# esp-wroom-32.net
KiCad netlist of a schematic drawn in Altium Designer
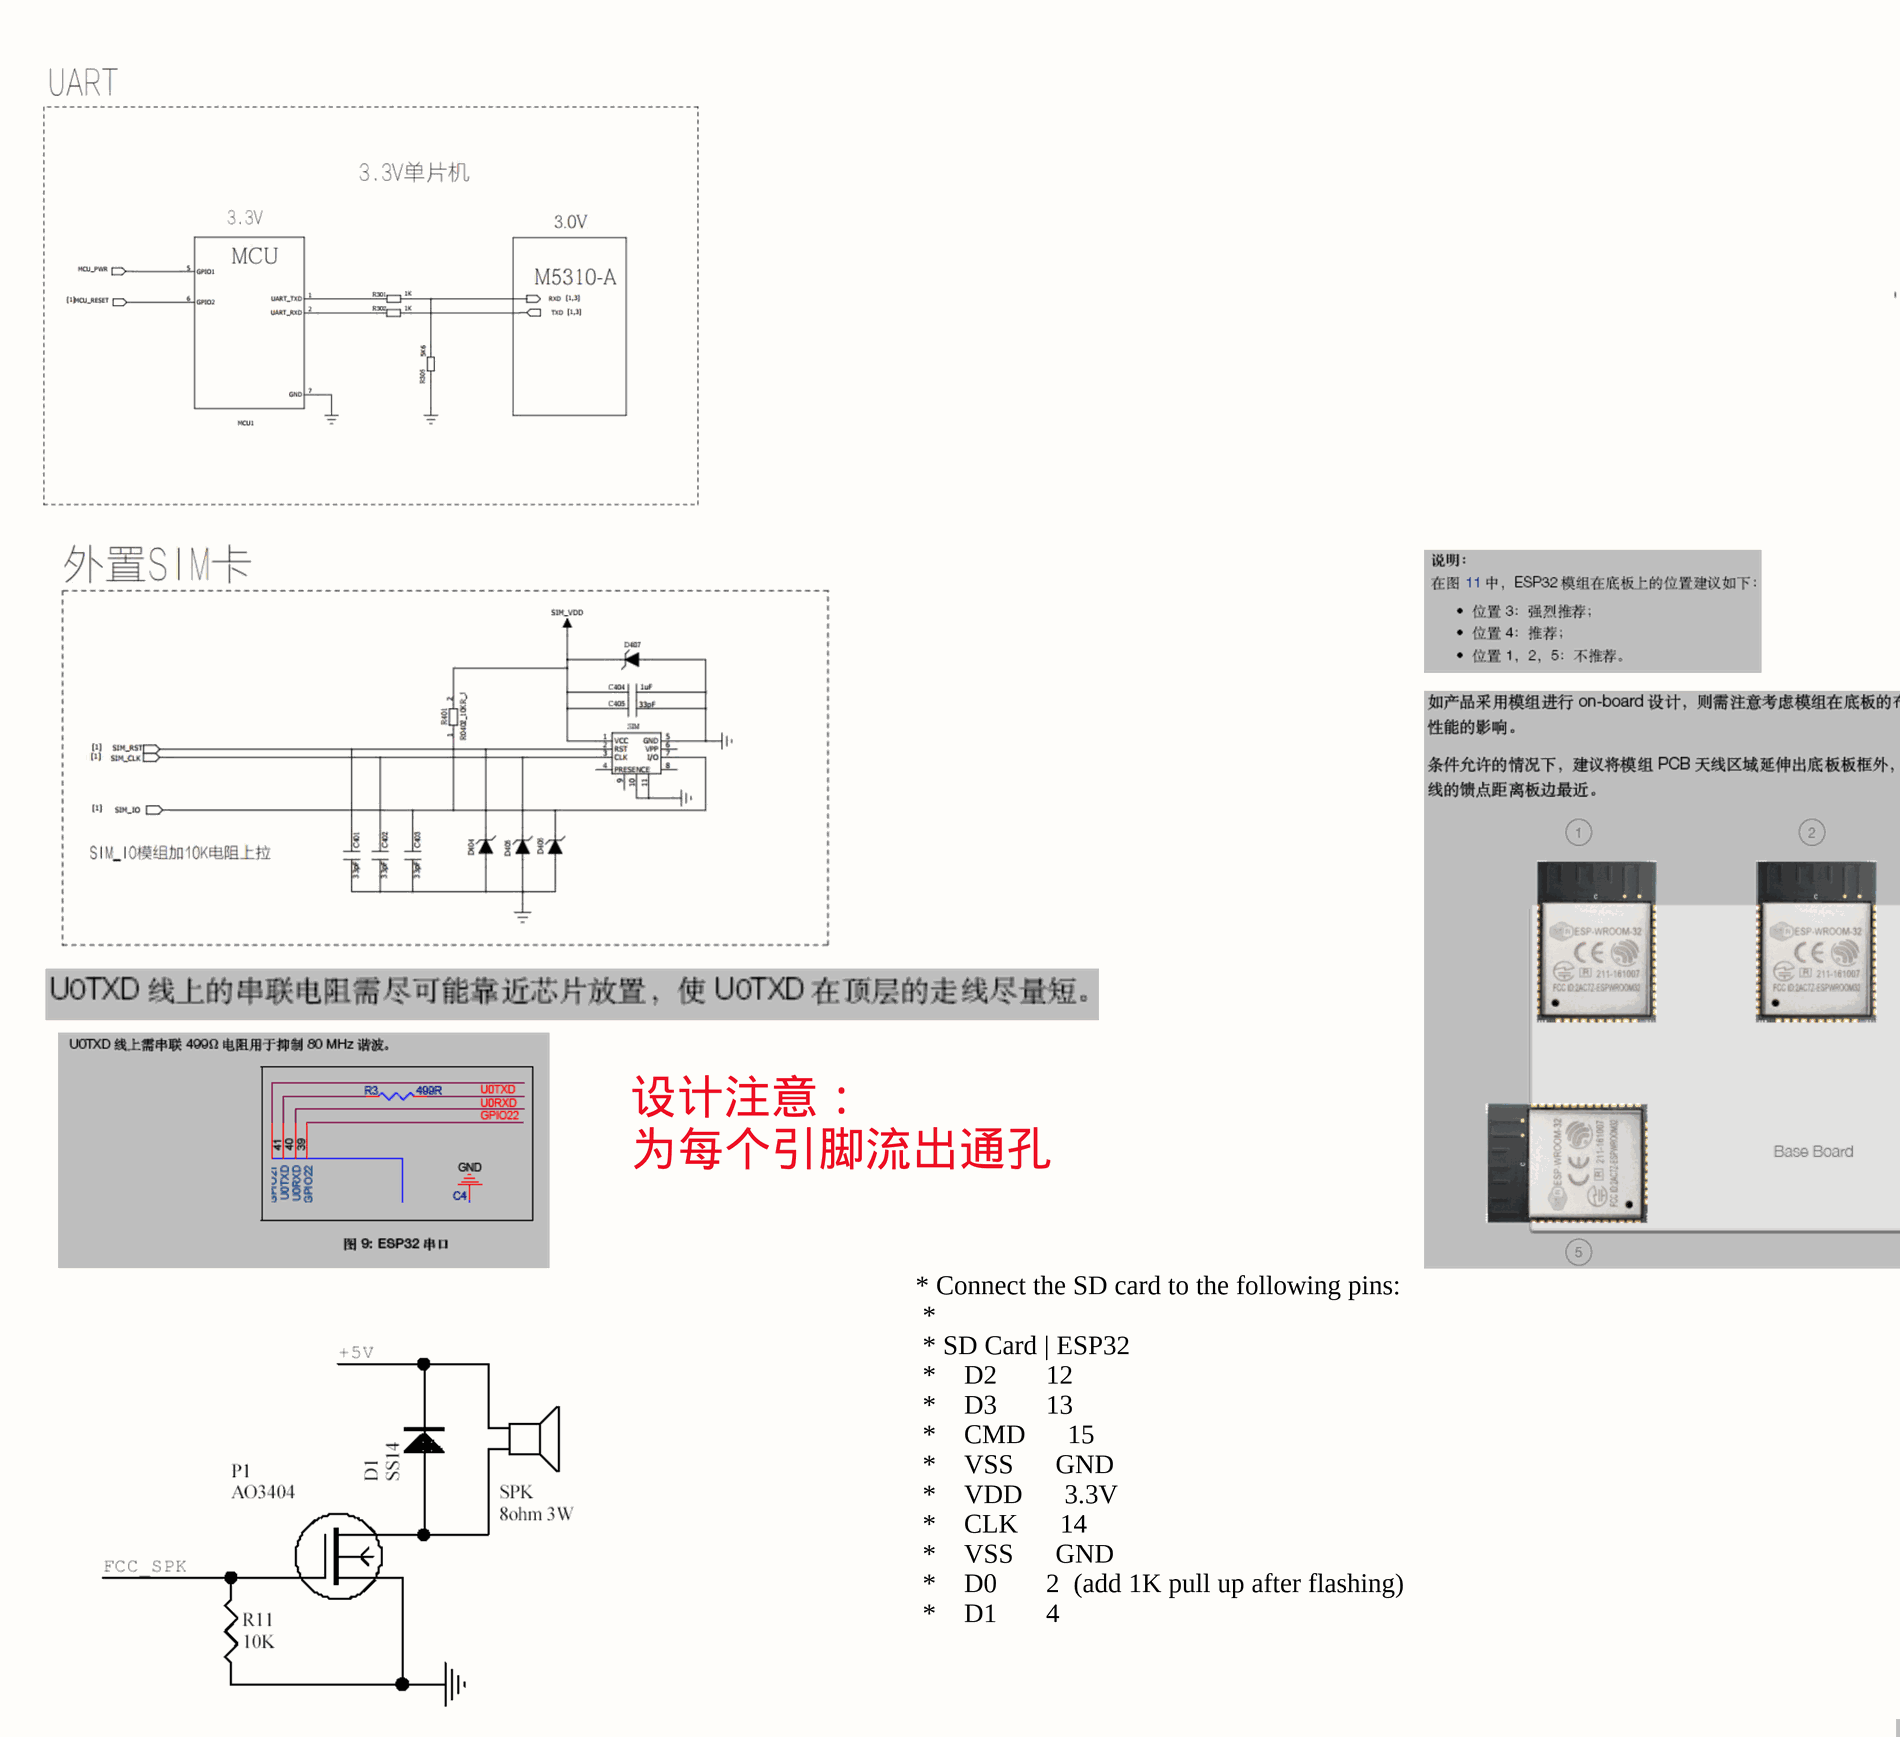
[diagram p0: esp-wroom-32.SchDoc, top left]
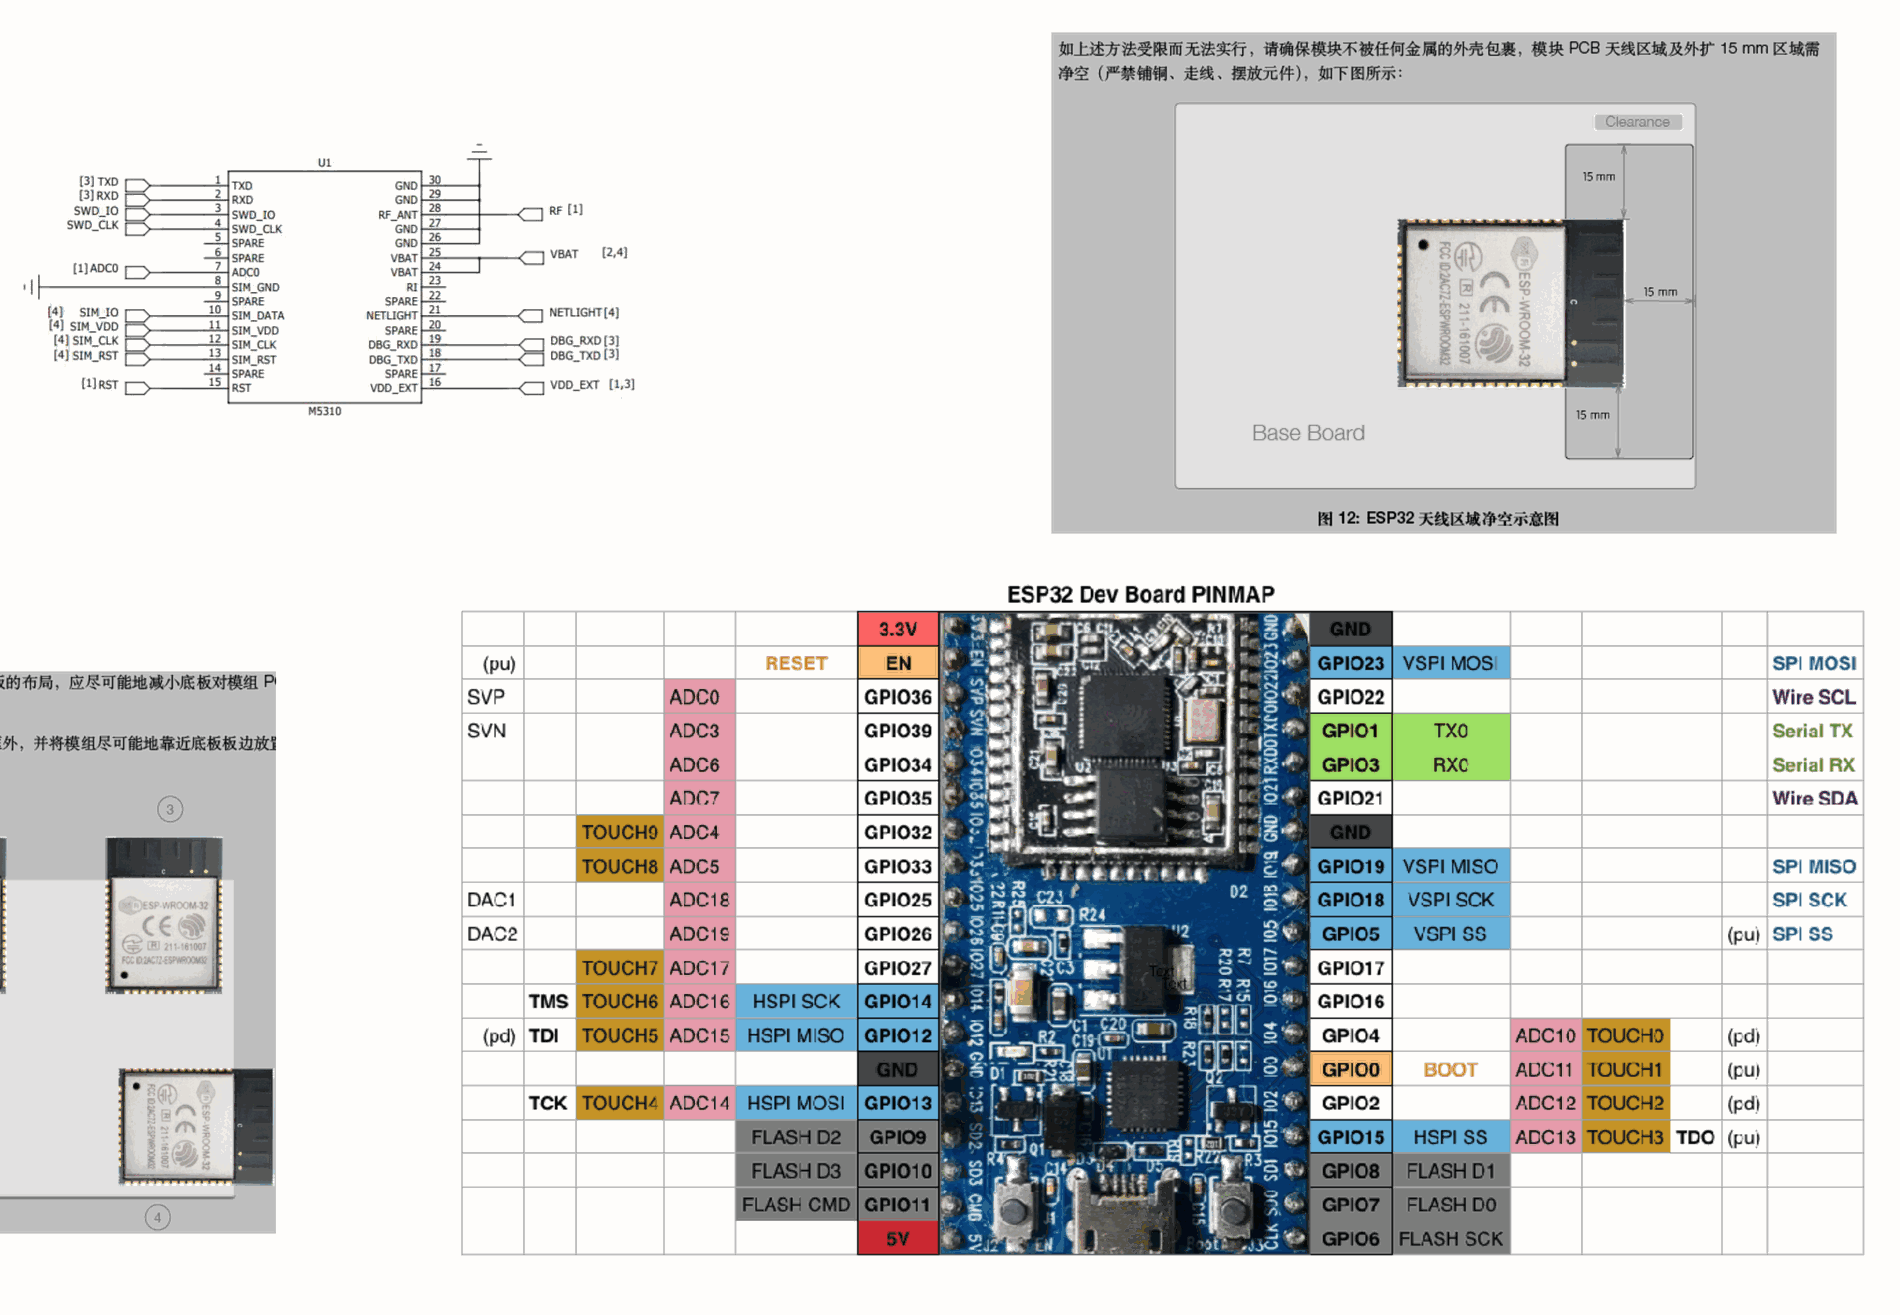
[diagram p1: esp-wroom-32.SchDoc, top right]
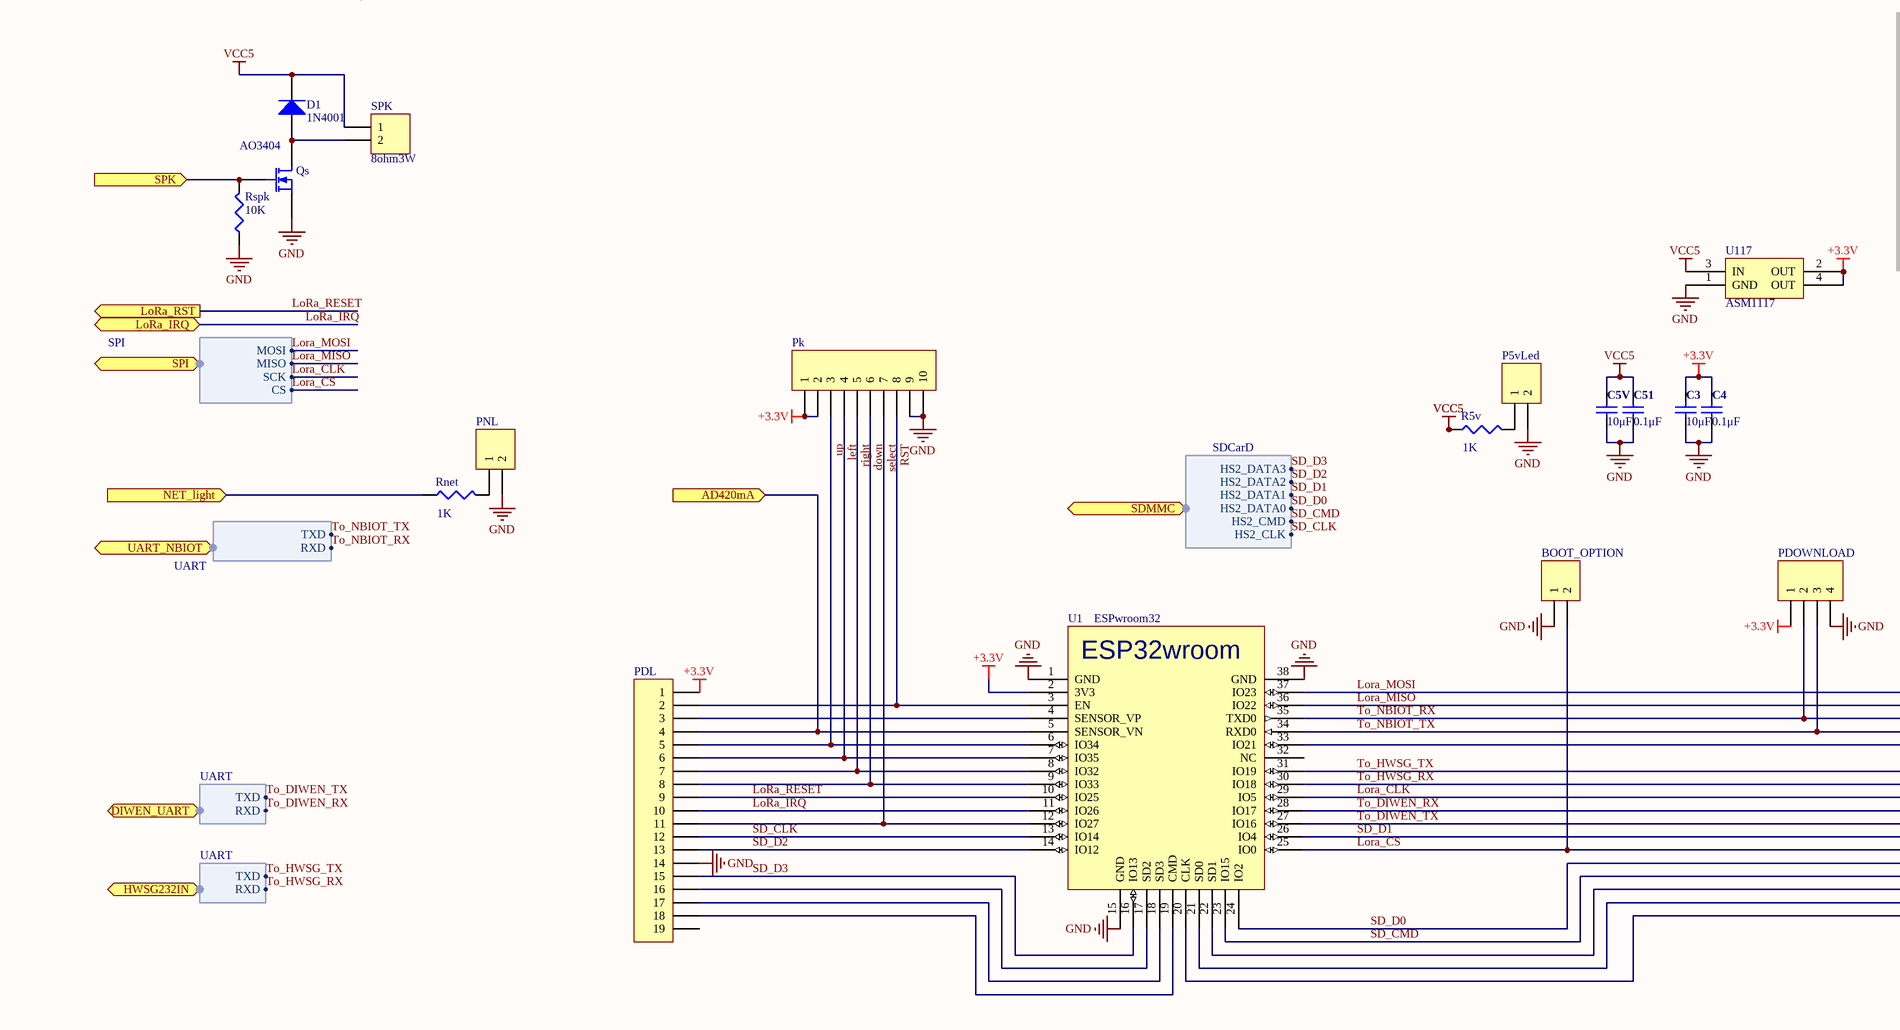
[diagram p2: esp-wroom-32.SchDoc, bottom left]
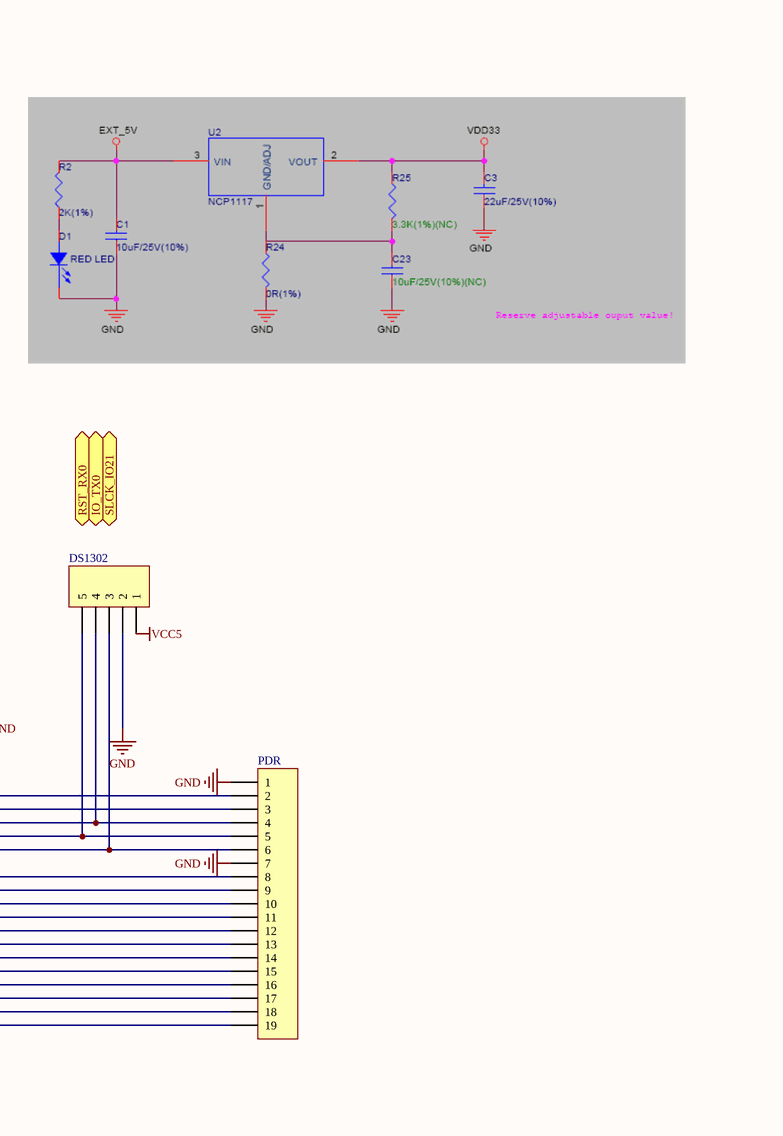
[diagram p3: esp-wroom-32.SchDoc, bottom right]

(export (version "E")
  (design (tool "Eeschema 10.0.6"))
  (components
    (comp (ref "BOOT_OPTION")
      (value "Header 2")
      (footprint "HDR1X2")
      (description "Header, 2-Pin")
      (fields (field (name "PUBLISHER") "Altium Limited"))
      (libsource (lib "Miscellaneous Connectors") (part "Header 2"))
    )
    (comp (ref "C3")
      (value "10μF")
      (footprint "CAP-7343")
      (description "贴片电容")
      (libsource (lib "FourAxis") (part "Cap"))
    )
    (comp (ref "C4")
      (value "0.1μF")
      (footprint "0805-1")
      (description "贴片电容")
      (libsource (lib "FourAxis") (part "Cap"))
    )
    (comp (ref "C5V")
      (value "10μF")
      (footprint "CAP-7343")
      (description "贴片电容")
      (libsource (lib "FourAxis") (part "Cap"))
    )
    (comp (ref "C51")
      (value "0.1μF")
      (footprint "0805-1")
      (description "贴片电容")
      (libsource (lib "FourAxis") (part "Cap"))
    )
    (comp (ref "D1")
      (value "SS14")
      (footprint "DIODE-1206")
      (description "二极管")
      (fields (field (name "TYPE") "1N4001") (field (name "PUBLISHER") "Altium Limited"))
      (libsource (lib "Fszhang") (part "Diode"))
    )
    (comp (ref "DS1302")
      (value "Header 5")
      (footprint "HDR1X5")
      (description "Header, 5-Pin")
      (fields (field (name "PUBLISHER") "Altium Limited"))
      (libsource (lib "Miscellaneous Connectors") (part "Header 5"))
    )
    (comp (ref "P5vLed")
      (value "Header 2")
      (footprint "HDR1X2")
      (description "Header, 2-Pin")
      (fields (field (name "PUBLISHER") "Altium Limited"))
      (libsource (lib "Miscellaneous Connectors") (part "Header 2"))
    )
    (comp (ref "PDL")
      (value "Header 19")
      (footprint "HDR1X19")
      (description "Header, 19-Pin")
      (fields (field (name "PUBLISHER") "Altium Limited"))
      (libsource (lib "Miscellaneous Connectors") (part "Header 19"))
    )
    (comp (ref "PDOWNLOAD")
      (value "Header 4")
      (footprint "HDR1X4")
      (description "Header, 4-Pin")
      (fields (field (name "PUBLISHER") "Altium Limited"))
      (libsource (lib "Miscellaneous Connectors") (part "Header 4"))
    )
    (comp (ref "PDR")
      (value "Header 19")
      (footprint "HDR1X19")
      (description "Header, 19-Pin")
      (fields (field (name "PUBLISHER") "Altium Limited"))
      (libsource (lib "") (part "Header 19_1"))
    )
    (comp (ref "Pk")
      (value "Header 10")
      (footprint "HDR1X10")
      (description "Header, 10-Pin")
      (fields (field (name "PUBLISHER") "Altium Limited"))
      (libsource (lib "Miscellaneous Connectors") (part "Header 10"))
    )
    (comp (ref "PNL")
      (value "Header 2")
      (footprint "HDR1X2")
      (description "Header, 2-Pin")
      (fields (field (name "PUBLISHER") "Altium Limited"))
      (libsource (lib "Miscellaneous Connectors") (part "Header 2"))
    )
    (comp (ref "Qs")
      (value "AO3404")
      (footprint "E3")
      (description "N-Channel MOSFET")
      (fields (field (name "PUBLISHER") "Altium Limited"))
      (libsource (lib "Miscellaneous Devices") (part "MOSFET-N"))
    )
    (comp (ref "R5v")
      (value "1K")
      (footprint "0805")
      (description "Resistor")
      (fields (field (name "Comment") "Res3") (field (name "PUBLISHER") "Altium Limited"))
      (libsource (lib "Miscellaneous Devices") (part "Res3"))
    )
    (comp (ref "Rnet")
      (value "1K")
      (footprint "0805")
      (description "Resistor")
      (fields (field (name "Comment") "Res3") (field (name "PUBLISHER") "Altium Limited"))
      (libsource (lib "Miscellaneous Devices") (part "Res3"))
    )
    (comp (ref "Rspk")
      (value "10K")
      (footprint "0805")
      (description "Resistor")
      (fields (field (name "Comment") "Res3") (field (name "PUBLISHER") "Altium Limited"))
      (libsource (lib "Miscellaneous Devices") (part "Res3"))
    )
    (comp (ref "SPK")
      (value "8ohm3W")
      (footprint "HDR1X2")
      (description "Header, 2-Pin")
      (fields (field (name "PUBLISHER") "Altium Limited"))
      (libsource (lib "") (part "Header 2_1"))
    )
    (comp (ref "U1")
      (value "ESPwroom32")
      (footprint "PCBComponent_1 - duplicate")
      (libsource (lib "ESPlib") (part "ESPwroom32"))
    )
    (comp (ref "U117")
      (value "ASM1117")
      (footprint "SOT-223")
      (description "3.3V稳压芯片")
      (libsource (lib "Fszhang") (part "ASM1117"))
    )
  )
  (nets
    (net (code "4") (name "+3.3V") (class "Default")
      (node (ref "C3") (pin "2") (pinfunction "2_2") (pintype "passive"))
      (node (ref "C4") (pin "2") (pinfunction "2_2") (pintype "passive"))
      (node (ref "PDL") (pin "1") (pinfunction "1_1") (pintype "passive"))
      (node (ref "PDOWNLOAD") (pin "1") (pinfunction "1_1") (pintype "passive"))
      (node (ref "Pk") (pin "1") (pinfunction "1_1") (pintype "passive"))
      (node (ref "Pk") (pin "2") (pinfunction "2_2") (pintype "passive"))
      (node (ref "U1") (pin "2") (pinfunction "3V3_2") (pintype "power_in"))
      (node (ref "U117") (pin "2") (pinfunction "OUT_2") (pintype "passive"))
      (node (ref "U117") (pin "4") (pinfunction "OUT_4") (pintype "passive"))
    )
    (net (code "5") (name "/AD420mA") (class "Default")
      (node (ref "PDL") (pin "4") (pinfunction "4_4") (pintype "passive"))
      (node (ref "U1") (pin "5") (pinfunction "SENSOR_VN_5") (pintype "passive"))
    )
    (net (code "7") (name "/LoRa_IRQ") (class "Default")
      (node (ref "PDL") (pin "10") (pinfunction "10_10") (pintype "passive"))
      (node (ref "U1") (pin "11") (pinfunction "IO26_11") (pintype "bidirectional"))
    )
    (net (code "8") (name "/LoRa_RESET") (class "Default")
      (node (ref "PDL") (pin "9") (pinfunction "9_9") (pintype "passive"))
      (node (ref "U1") (pin "10") (pinfunction "IO25_10") (pintype "bidirectional"))
    )
    (net (code "9") (name "/Lora_CLK") (class "Default")
      (node (ref "PDR") (pin "10") (pinfunction "10_10") (pintype "passive"))
      (node (ref "U1") (pin "29") (pinfunction "IO5_29") (pintype "bidirectional"))
    )
    (net (code "10") (name "/Lora_CS") (class "Default")
      (node (ref "BOOT_OPTION") (pin "2") (pinfunction "2_2") (pintype "passive"))
      (node (ref "PDR") (pin "14") (pinfunction "14_14") (pintype "passive"))
      (node (ref "U1") (pin "25") (pinfunction "IO0_25") (pintype "bidirectional"))
    )
    (net (code "11") (name "/Lora_MISO") (class "Default")
      (node (ref "PDR") (pin "3") (pinfunction "3_3") (pintype "passive"))
      (node (ref "U1") (pin "36") (pinfunction "IO22_36") (pintype "bidirectional"))
    )
    (net (code "12") (name "/Lora_MOSI") (class "Default")
      (node (ref "PDR") (pin "2") (pinfunction "2_2") (pintype "passive"))
      (node (ref "U1") (pin "37") (pinfunction "IO23_37") (pintype "bidirectional"))
    )
    (net (code "13") (name "/NET_light") (class "Default")
      (node (ref "Rnet") (pin "1") (pinfunction "1_1") (pintype "passive"))
    )
    (net (code "14") (name "/RST") (class "Default")
      (node (ref "PDL") (pin "2") (pinfunction "2_2") (pintype "passive"))
      (node (ref "Pk") (pin "8") (pinfunction "8_8") (pintype "passive"))
      (node (ref "U1") (pin "3") (pinfunction "EN_3") (pintype "passive"))
    )
    (net (code "16") (name "/SD_CLK") (class "Default")
      (node (ref "PDL") (pin "12") (pinfunction "12_12") (pintype "passive"))
      (node (ref "U1") (pin "13") (pinfunction "IO14_13") (pintype "bidirectional"))
    )
    (net (code "17") (name "/SD_CMD") (class "Default")
      (node (ref "PDR") (pin "16") (pinfunction "16_16") (pintype "passive"))
      (node (ref "U1") (pin "23") (pinfunction "IO15_23") (pintype "passive"))
    )
    (net (code "18") (name "/SD_D0") (class "Default")
      (node (ref "PDR") (pin "15") (pinfunction "15_15") (pintype "passive"))
      (node (ref "U1") (pin "24") (pinfunction "IO2_24") (pintype "passive"))
    )
    (net (code "19") (name "/SD_D1") (class "Default")
      (node (ref "PDR") (pin "13") (pinfunction "13_13") (pintype "passive"))
      (node (ref "U1") (pin "26") (pinfunction "IO4_26") (pintype "bidirectional"))
    )
    (net (code "20") (name "/SD_D2") (class "Default")
      (node (ref "PDL") (pin "13") (pinfunction "13_13") (pintype "passive"))
      (node (ref "U1") (pin "14") (pinfunction "IO12_14") (pintype "bidirectional"))
    )
    (net (code "21") (name "/SD_D3") (class "Default")
      (node (ref "PDL") (pin "15") (pinfunction "15_15") (pintype "passive"))
      (node (ref "U1") (pin "16") (pinfunction "IO13_16") (pintype "bidirectional"))
    )
    (net (code "23") (name "/SPK") (class "Default")
      (node (ref "Qs") (pin "2") (pinfunction "G_2") (pintype "passive"))
      (node (ref "Rspk") (pin "2") (pinfunction "2_2") (pintype "passive"))
    )
    (net (code "24") (name "/To_DIWEN_RX") (class "Default")
      (node (ref "PDR") (pin "11") (pinfunction "11_11") (pintype "passive"))
      (node (ref "U1") (pin "28") (pinfunction "IO17_28") (pintype "bidirectional"))
    )
    (net (code "25") (name "/To_DIWEN_TX") (class "Default")
      (node (ref "PDR") (pin "12") (pinfunction "12_12") (pintype "passive"))
      (node (ref "U1") (pin "27") (pinfunction "IO16_27") (pintype "bidirectional"))
    )
    (net (code "26") (name "/To_HWSG_RX") (class "Default")
      (node (ref "PDR") (pin "9") (pinfunction "9_9") (pintype "passive"))
      (node (ref "U1") (pin "30") (pinfunction "IO18_30") (pintype "bidirectional"))
    )
    (net (code "27") (name "/To_HWSG_TX") (class "Default")
      (node (ref "PDR") (pin "8") (pinfunction "8_8") (pintype "passive"))
      (node (ref "U1") (pin "31") (pinfunction "IO19_31") (pintype "bidirectional"))
    )
    (net (code "28") (name "/To_NBIOT_RX") (class "Default")
      (node (ref "DS1302") (pin "4") (pinfunction "4_4") (pintype "passive"))
      (node (ref "PDOWNLOAD") (pin "2") (pinfunction "2_2") (pintype "passive"))
      (node (ref "PDR") (pin "4") (pinfunction "4_4") (pintype "passive"))
      (node (ref "U1") (pin "35") (pinfunction "TXD0_35") (pintype "output"))
    )
    (net (code "29") (name "/To_NBIOT_TX") (class "Default")
      (node (ref "DS1302") (pin "5") (pinfunction "5_5") (pintype "passive"))
      (node (ref "PDOWNLOAD") (pin "3") (pinfunction "3_3") (pintype "passive"))
      (node (ref "PDR") (pin "5") (pinfunction "5_5") (pintype "passive"))
      (node (ref "U1") (pin "34") (pinfunction "RXD0_34") (pintype "input"))
    )
    (net (code "30") (name "/down") (class "Default")
      (node (ref "PDL") (pin "8") (pinfunction "8_8") (pintype "passive"))
      (node (ref "Pk") (pin "6") (pinfunction "6_6") (pintype "passive"))
      (node (ref "U1") (pin "9") (pinfunction "IO33_9") (pintype "bidirectional"))
    )
    (net (code "31") (name "/left") (class "Default")
      (node (ref "PDL") (pin "6") (pinfunction "6_6") (pintype "passive"))
      (node (ref "Pk") (pin "4") (pinfunction "4_4") (pintype "passive"))
      (node (ref "U1") (pin "7") (pinfunction "IO35_7") (pintype "bidirectional"))
    )
    (net (code "32") (name "/right") (class "Default")
      (node (ref "PDL") (pin "7") (pinfunction "7_7") (pintype "passive"))
      (node (ref "Pk") (pin "5") (pinfunction "5_5") (pintype "passive"))
      (node (ref "U1") (pin "8") (pinfunction "IO32_8") (pintype "bidirectional"))
    )
    (net (code "33") (name "/select") (class "Default")
      (node (ref "PDL") (pin "11") (pinfunction "11_11") (pintype "passive"))
      (node (ref "Pk") (pin "7") (pinfunction "7_7") (pintype "passive"))
      (node (ref "U1") (pin "12") (pinfunction "IO27_12") (pintype "bidirectional"))
    )
    (net (code "34") (name "/up") (class "Default")
      (node (ref "PDL") (pin "5") (pinfunction "5_5") (pintype "passive"))
      (node (ref "Pk") (pin "3") (pinfunction "3_3") (pintype "passive"))
      (node (ref "U1") (pin "6") (pinfunction "IO34_6") (pintype "bidirectional"))
    )
    (net (code "38") (name "GND") (class "Default")
      (node (ref "BOOT_OPTION") (pin "1") (pinfunction "1_1") (pintype "passive"))
      (node (ref "C3") (pin "1") (pinfunction "1_1") (pintype "passive"))
      (node (ref "C4") (pin "1") (pinfunction "1_1") (pintype "passive"))
      (node (ref "C51") (pin "1") (pinfunction "1_1") (pintype "passive"))
      (node (ref "C5V") (pin "1") (pinfunction "1_1") (pintype "passive"))
      (node (ref "DS1302") (pin "2") (pinfunction "2_2") (pintype "passive"))
      (node (ref "P5vLed") (pin "2") (pinfunction "2_2") (pintype "passive"))
      (node (ref "PDL") (pin "14") (pinfunction "14_14") (pintype "passive"))
      (node (ref "PDOWNLOAD") (pin "4") (pinfunction "4_4") (pintype "passive"))
      (node (ref "PDR") (pin "1") (pinfunction "1_1") (pintype "passive"))
      (node (ref "PDR") (pin "7") (pinfunction "7_7") (pintype "passive"))
      (node (ref "PNL") (pin "2") (pinfunction "2_2") (pintype "passive"))
      (node (ref "Pk") (pin "10") (pinfunction "10_10") (pintype "passive"))
      (node (ref "Pk") (pin "9") (pinfunction "9_9") (pintype "passive"))
      (node (ref "Qs") (pin "3") (pinfunction "S_3") (pintype "passive"))
      (node (ref "Rspk") (pin "1") (pinfunction "1_1") (pintype "passive"))
      (node (ref "U1") (pin "1") (pinfunction "GND_1") (pintype "power_in"))
      (node (ref "U1") (pin "15") (pinfunction "GND_15") (pintype "power_in"))
      (node (ref "U1") (pin "38") (pinfunction "GND_38") (pintype "power_in"))
      (node (ref "U117") (pin "1") (pinfunction "GND_1") (pintype "passive"))
    )
    (net (code "39") (name "Net-(D1-A)") (class "Default")
      (node (ref "D1") (pin "1") (pinfunction "A_1") (pintype "passive"))
      (node (ref "Qs") (pin "1") (pinfunction "D_1") (pintype "passive"))
      (node (ref "SPK") (pin "2") (pinfunction "2_2") (pintype "passive"))
    )
    (net (code "40") (name "Net-(P5vLed-Pad1)") (class "Default")
      (node (ref "P5vLed") (pin "1") (pinfunction "1_1") (pintype "passive"))
      (node (ref "R5v") (pin "2") (pinfunction "2_2") (pintype "passive"))
    )
    (net (code "41") (name "Net-(PNL-Pad1)") (class "Default")
      (node (ref "PNL") (pin "1") (pinfunction "1_1") (pintype "passive"))
      (node (ref "Rnet") (pin "2") (pinfunction "2_2") (pintype "passive"))
    )
    (net (code "42") (name "Net-(U1-CLK)") (class "Default")
      (node (ref "PDR") (pin "19") (pinfunction "19_19") (pintype "passive"))
      (node (ref "U1") (pin "20") (pinfunction "CLK_20") (pintype "passive"))
    )
    (net (code "43") (name "Net-(U1-CMD)") (class "Default")
      (node (ref "PDL") (pin "18") (pinfunction "18_18") (pintype "passive"))
      (node (ref "U1") (pin "19") (pinfunction "CMD_19") (pintype "passive"))
    )
    (net (code "44") (name "Net-(U1-IO21)") (class "Default")
      (node (ref "DS1302") (pin "3") (pinfunction "3_3") (pintype "passive"))
      (node (ref "PDR") (pin "6") (pinfunction "6_6") (pintype "passive"))
      (node (ref "U1") (pin "33") (pinfunction "IO21_33") (pintype "bidirectional"))
    )
    (net (code "45") (name "Net-(U1-SD0)") (class "Default")
      (node (ref "PDR") (pin "18") (pinfunction "18_18") (pintype "passive"))
      (node (ref "U1") (pin "21") (pinfunction "SD0_21") (pintype "passive"))
    )
    (net (code "46") (name "Net-(U1-SD1)") (class "Default")
      (node (ref "PDR") (pin "17") (pinfunction "17_17") (pintype "passive"))
      (node (ref "U1") (pin "22") (pinfunction "SD1_22") (pintype "passive"))
    )
    (net (code "47") (name "Net-(U1-SD2)") (class "Default")
      (node (ref "PDL") (pin "16") (pinfunction "16_16") (pintype "passive"))
      (node (ref "U1") (pin "17") (pinfunction "SD2_17") (pintype "passive"))
    )
    (net (code "48") (name "Net-(U1-SD3)") (class "Default")
      (node (ref "PDL") (pin "17") (pinfunction "17_17") (pintype "passive"))
      (node (ref "U1") (pin "18") (pinfunction "SD3_18") (pintype "passive"))
    )
    (net (code "49") (name "Net-(U1-SENSOR_VP)") (class "Default")
      (node (ref "PDL") (pin "3") (pinfunction "3_3") (pintype "passive"))
      (node (ref "U1") (pin "4") (pinfunction "SENSOR_VP_4") (pintype "passive"))
    )
    (net (code "50") (name "VCC5") (class "Default")
      (node (ref "C51") (pin "2") (pinfunction "2_2") (pintype "passive"))
      (node (ref "C5V") (pin "2") (pinfunction "2_2") (pintype "passive"))
      (node (ref "D1") (pin "2") (pinfunction "K_2") (pintype "passive"))
      (node (ref "DS1302") (pin "1") (pinfunction "1_1") (pintype "passive"))
      (node (ref "R5v") (pin "1") (pinfunction "1_1") (pintype "passive"))
      (node (ref "SPK") (pin "1") (pinfunction "1_1") (pintype "passive"))
      (node (ref "U117") (pin "3") (pinfunction "IN_3") (pintype "passive"))
    )
    (net (code "51") (name "unconnected-(PDL-Pad19)") (class "Default")
      (node (ref "PDL") (pin "19") (pinfunction "19_19") (pintype "passive"))
    )
    (net (code "52") (name "unconnected-(U1-NC-Pad32)") (class "Default")
      (node (ref "U1") (pin "32") (pinfunction "NC_32") (pintype "passive"))
    )
  )
)
